# Qwiic_GPS_-_Ublox_SAM-M8Q_-_EAGLE_ARRRG.net
KiCad netlist of a schematic drawn in EAGLE
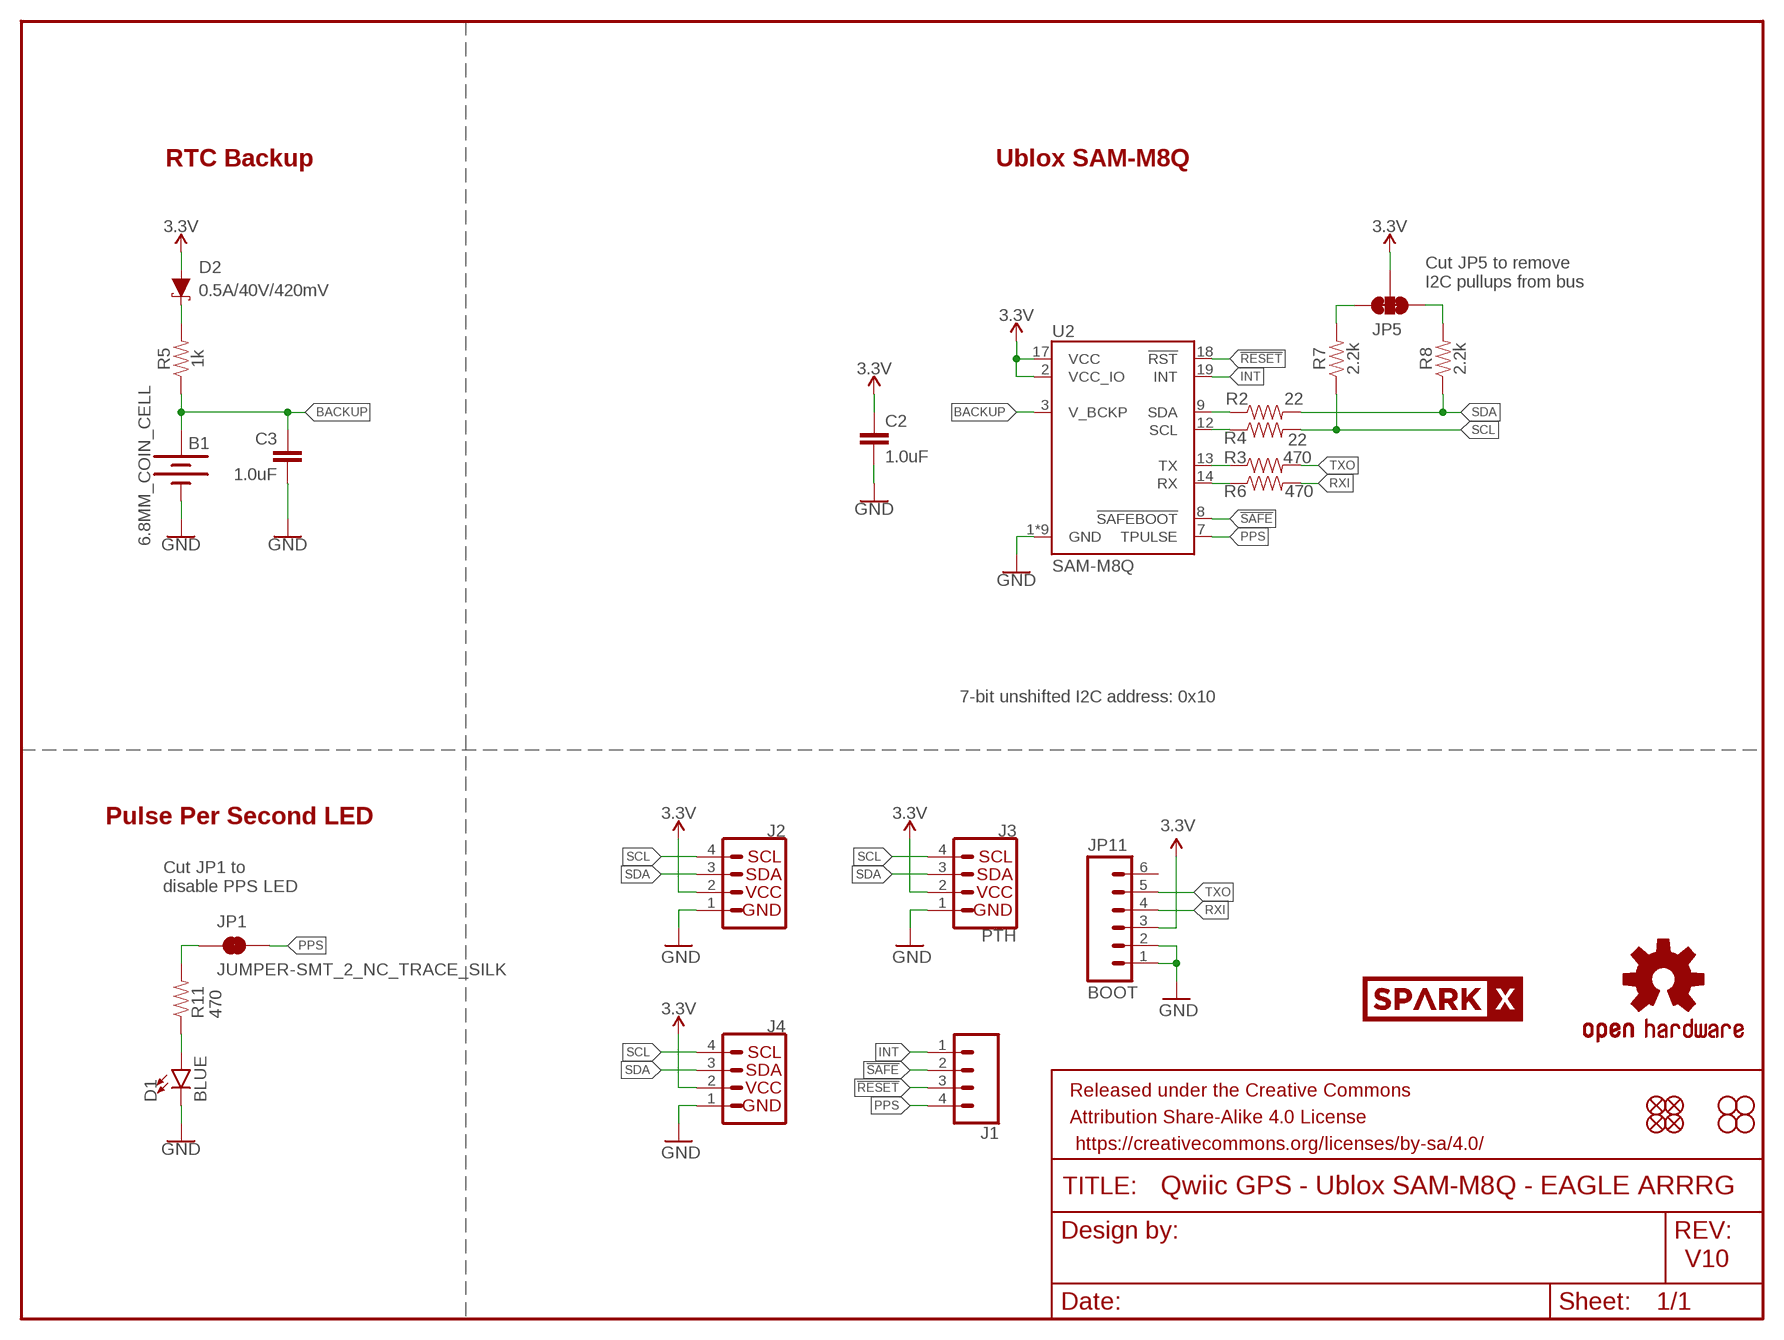
[diagram p0: schematic, sheet 1]

(export (version "E")
  (design (tool "Eeschema 10.0.6"))
  (components
    (comp (ref "B1")
      (value "6.8MM_COIN_CELL")
      (footprint "eagle-import:BATTCON-6.8MM")
      (libsource (lib "eagle-import") (part "BATTERY-6.8MM_SMD"))
    )
    (comp (ref "C2")
      (value "1.0uF")
      (footprint "eagle-import:0603")
      (libsource (lib "eagle-import") (part "1.0UF-0603-16V-10%"))
    )
    (comp (ref "C3")
      (value "1.0uF")
      (footprint "eagle-import:0603")
      (libsource (lib "eagle-import") (part "1.0UF-0603-16V-10%"))
    )
    (comp (ref "D1")
      (value "BLUE")
      (footprint "eagle-import:LED-0603")
      (libsource (lib "eagle-import") (part "LED-BLUE0603"))
    )
    (comp (ref "D2")
      (value "0.5A/40V/420mV")
      (footprint "eagle-import:SOD-323")
      (libsource (lib "eagle-import") (part "DIODE-SCHOTTKY-PMEG4005EJ"))
    )
    (comp (ref "FRAME1")
      (value "FRAME-LETTER")
      (footprint "eagle-import:CREATIVE_COMMONS")
      (libsource (lib "eagle-import") (part "FRAME-LETTER"))
    )
    (comp (ref "J1")
      (value "CONN_041X04_NO_SILK")
      (footprint "eagle-import:1X04_NO_SILK")
      (libsource (lib "eagle-import") (part "CONN_041X04_NO_SILK"))
    )
    (comp (ref "J2")
      (value "I2C_STANDARDQWIIC")
      (footprint "eagle-import:1X04_1MM_RA")
      (libsource (lib "eagle-import") (part "I2C_STANDARDQWIIC"))
    )
    (comp (ref "J3")
      (value "PTH")
      (footprint "eagle-import:1X04_NO_SILK")
      (libsource (lib "eagle-import") (part "SparkX_I2C_STANDARD_NO_SILK"))
    )
    (comp (ref "J4")
      (value "I2C_STANDARDQWIIC")
      (footprint "eagle-import:1X04_1MM_RA")
      (libsource (lib "eagle-import") (part "I2C_STANDARDQWIIC"))
    )
    (comp (ref "JP1")
      (value "JUMPER-SMT_2_NC_TRACE_SILK")
      (footprint "eagle-import:SMT-JUMPER_2_NC_TRACE_SILK")
      (libsource (lib "eagle-import") (part "JUMPER-SMT_2_NC_TRACE_SILK"))
    )
    (comp (ref "JP2")
      (value "FIDUCIALUFIDUCIAL")
      (footprint "eagle-import:MICRO-FIDUCIAL")
      (libsource (lib "eagle-import") (part "FIDUCIALUFIDUCIAL"))
    )
    (comp (ref "JP3")
      (value "STAND-OFF")
      (footprint "eagle-import:STAND-OFF")
      (libsource (lib "eagle-import") (part "STAND-OFF"))
    )
    (comp (ref "JP4")
      (value "STAND-OFF")
      (footprint "eagle-import:STAND-OFF")
      (libsource (lib "eagle-import") (part "STAND-OFF"))
    )
    (comp (ref "JP5")
      (value "JUMPER-SMT_3_2-NC_TRACE_SILK")
      (footprint "eagle-import:SMT-JUMPER_3_2-NC_TRACE_SILK")
      (libsource (lib "eagle-import") (part "JUMPER-SMT_3_2-NC_TRACE_SILK"))
    )
    (comp (ref "JP6")
      (value "FIDUCIALUFIDUCIAL")
      (footprint "eagle-import:MICRO-FIDUCIAL")
      (libsource (lib "eagle-import") (part "FIDUCIALUFIDUCIAL"))
    )
    (comp (ref "JP7")
      (value "FIDUCIALUFIDUCIAL")
      (footprint "eagle-import:MICRO-FIDUCIAL")
      (libsource (lib "eagle-import") (part "FIDUCIALUFIDUCIAL"))
    )
    (comp (ref "JP8")
      (value "FIDUCIALUFIDUCIAL")
      (footprint "eagle-import:MICRO-FIDUCIAL")
      (libsource (lib "eagle-import") (part "FIDUCIALUFIDUCIAL"))
    )
    (comp (ref "JP9")
      (value "STAND-OFF")
      (footprint "eagle-import:STAND-OFF")
      (libsource (lib "eagle-import") (part "STAND-OFF"))
    )
    (comp (ref "JP10")
      (value "STAND-OFF")
      (footprint "eagle-import:STAND-OFF")
      (libsource (lib "eagle-import") (part "STAND-OFF"))
    )
    (comp (ref "JP11")
      (value "BOOT")
      (footprint "eagle-import:1X06_NO_SILK")
      (libsource (lib "eagle-import") (part "M06NO_SILK_FEMALE_PTH"))
    )
    (comp (ref "LOGO1")
      (value "OSHW-LOGOMINI")
      (footprint "eagle-import:OSHW-LOGO-MINI")
      (libsource (lib "eagle-import") (part "OSHW-LOGOMINI"))
    )
    (comp (ref "R2")
      (value "22")
      (footprint "eagle-import:0603")
      (libsource (lib "eagle-import") (part "22OHM-0603-1/10W-1%"))
    )
    (comp (ref "R3")
      (value "470")
      (footprint "eagle-import:0603")
      (libsource (lib "eagle-import") (part "470OHM-0603-1/10W-1%"))
    )
    (comp (ref "R4")
      (value "22")
      (footprint "eagle-import:0603")
      (libsource (lib "eagle-import") (part "22OHM-0603-1/10W-1%"))
    )
    (comp (ref "R5")
      (value "1k")
      (footprint "eagle-import:0603")
      (libsource (lib "eagle-import") (part "1KOHM-0603-1/10W-1%"))
    )
    (comp (ref "R6")
      (value "470")
      (footprint "eagle-import:0603")
      (libsource (lib "eagle-import") (part "470OHM-0603-1/10W-1%"))
    )
    (comp (ref "R7")
      (value "2.2k")
      (footprint "eagle-import:0603")
      (libsource (lib "eagle-import") (part "2.2KOHM-0603-1/10W-1%"))
    )
    (comp (ref "R8")
      (value "2.2k")
      (footprint "eagle-import:0603")
      (libsource (lib "eagle-import") (part "2.2KOHM-0603-1/10W-1%"))
    )
    (comp (ref "R11")
      (value "470")
      (footprint "eagle-import:0603")
      (libsource (lib "eagle-import") (part "470OHM-0603-1/10W-1%"))
    )
    (comp (ref "U$31")
      (value "SPARKX-LOGO4")
      (footprint "eagle-import:SPARKX-MEDIUM")
      (libsource (lib "eagle-import") (part "SPARKX-LOGO4"))
    )
    (comp (ref "U2")
      (value "SAM-M8Q")
      (footprint "eagle-import:SAM-M8Q")
      (libsource (lib "eagle-import") (part "SAM-M8Q"))
    )
  )
  (nets
    (net (code "1") (name "/~{RESET}") (class "Default")
      (node (ref "J1") (pin "3") (pinfunction "3_3") (pintype "passive"))
      (node (ref "U2") (pin "18") (pinfunction "~{RST}_18") (pintype "bidirectional"))
    )
    (net (code "2") (name "/~{SAFE}") (class "Default")
      (node (ref "J1") (pin "2") (pinfunction "2_2") (pintype "passive"))
      (node (ref "U2") (pin "8") (pinfunction "~{SAFEBOOT}_8") (pintype "bidirectional"))
    )
    (net (code "3") (name "3.3V") (class "Default")
      (node (ref "C2") (pin "1") (pinfunction "1_1") (pintype "passive"))
      (node (ref "D2") (pin "A") (pinfunction "A_A") (pintype "passive"))
      (node (ref "J2") (pin "2") (pinfunction "2_2") (pintype "power_in"))
      (node (ref "J3") (pin "2") (pinfunction "VCC_2") (pintype "power_in"))
      (node (ref "J4") (pin "2") (pinfunction "2_2") (pintype "power_in"))
      (node (ref "JP11") (pin "3") (pinfunction "3_3") (pintype "passive"))
      (node (ref "JP5") (pin "2") (pinfunction "2_2") (pintype "passive"))
      (node (ref "U2") (pin "17") (pinfunction "VCC_17") (pintype "bidirectional"))
      (node (ref "U2") (pin "2") (pinfunction "VCC_IO_2") (pintype "bidirectional"))
    )
    (net (code "4") (name "BACKUP") (class "Default")
      (node (ref "B1") (pin "+") (pinfunction "+_+") (pintype "power_in"))
      (node (ref "C3") (pin "1") (pinfunction "1_1") (pintype "passive"))
      (node (ref "R5") (pin "1") (pinfunction "1_1") (pintype "passive"))
      (node (ref "U2") (pin "3") (pinfunction "V_BCKP_3") (pintype "bidirectional"))
    )
    (net (code "5") (name "GND") (class "Default")
      (node (ref "B1") (pin "-") (pinfunction "-_-") (pintype "power_in"))
      (node (ref "C2") (pin "2") (pinfunction "2_2") (pintype "passive"))
      (node (ref "C3") (pin "2") (pinfunction "2_2") (pintype "passive"))
      (node (ref "D1") (pin "C") (pinfunction "C_C") (pintype "passive"))
      (node (ref "J2") (pin "1") (pinfunction "1_1") (pintype "power_in"))
      (node (ref "J3") (pin "1") (pinfunction "GND_1") (pintype "power_in"))
      (node (ref "J4") (pin "1") (pinfunction "1_1") (pintype "power_in"))
      (node (ref "JP11") (pin "1") (pinfunction "1_1") (pintype "passive"))
      (node (ref "JP11") (pin "2") (pinfunction "2_2") (pintype "passive"))
      (node (ref "U2") (pin "1") (pinfunction "GND_1") (pintype "bidirectional"))
      (node (ref "U2") (pin "10") (pinfunction "GND_10") (pintype "bidirectional"))
      (node (ref "U2") (pin "11") (pinfunction "GND_11") (pintype "bidirectional"))
      (node (ref "U2") (pin "15") (pinfunction "GND_15") (pintype "bidirectional"))
      (node (ref "U2") (pin "16") (pinfunction "GND_16") (pintype "bidirectional"))
      (node (ref "U2") (pin "20") (pinfunction "GND_20") (pintype "bidirectional"))
      (node (ref "U2") (pin "4") (pinfunction "GND_4") (pintype "bidirectional"))
      (node (ref "U2") (pin "5") (pinfunction "GND_5") (pintype "bidirectional"))
      (node (ref "U2") (pin "6") (pinfunction "GND_6") (pintype "bidirectional"))
    )
    (net (code "6") (name "INT") (class "Default")
      (node (ref "J1") (pin "1") (pinfunction "1_1") (pintype "passive"))
      (node (ref "U2") (pin "19") (pinfunction "INT_19") (pintype "bidirectional"))
    )
    (net (code "7") (name "Net-(D1-PadA)") (class "Default")
      (node (ref "D1") (pin "A") (pinfunction "A_A") (pintype "passive"))
      (node (ref "R11") (pin "1") (pinfunction "1_1") (pintype "passive"))
    )
    (net (code "8") (name "Net-(D2-PadC)") (class "Default")
      (node (ref "D2") (pin "C") (pinfunction "C_C") (pintype "passive"))
      (node (ref "R5") (pin "2") (pinfunction "2_2") (pintype "passive"))
    )
    (net (code "9") (name "Net-(JP1-Pad1)") (class "Default")
      (node (ref "JP1") (pin "1") (pinfunction "1_1") (pintype "passive"))
      (node (ref "R11") (pin "2") (pinfunction "2_2") (pintype "passive"))
    )
    (net (code "10") (name "Net-(JP5-Pad1)") (class "Default")
      (node (ref "JP5") (pin "1") (pinfunction "1_1") (pintype "passive"))
      (node (ref "R8") (pin "2") (pinfunction "2_2") (pintype "passive"))
    )
    (net (code "11") (name "Net-(JP5-Pad3)") (class "Default")
      (node (ref "JP5") (pin "3") (pinfunction "3_3") (pintype "passive"))
      (node (ref "R7") (pin "2") (pinfunction "2_2") (pintype "passive"))
    )
    (net (code "12") (name "Net-(U2-RX)") (class "Default")
      (node (ref "R6") (pin "1") (pinfunction "1_1") (pintype "passive"))
      (node (ref "U2") (pin "14") (pinfunction "RX_14") (pintype "bidirectional"))
    )
    (net (code "13") (name "Net-(U2-SCL)") (class "Default")
      (node (ref "R4") (pin "1") (pinfunction "1_1") (pintype "passive"))
      (node (ref "U2") (pin "12") (pinfunction "SCL_12") (pintype "bidirectional"))
    )
    (net (code "14") (name "Net-(U2-SDA)") (class "Default")
      (node (ref "R2") (pin "1") (pinfunction "1_1") (pintype "passive"))
      (node (ref "U2") (pin "9") (pinfunction "SDA_9") (pintype "bidirectional"))
    )
    (net (code "15") (name "Net-(U2-TX)") (class "Default")
      (node (ref "R3") (pin "1") (pinfunction "1_1") (pintype "passive"))
      (node (ref "U2") (pin "13") (pinfunction "TX_13") (pintype "bidirectional"))
    )
    (net (code "16") (name "PPS") (class "Default")
      (node (ref "J1") (pin "4") (pinfunction "4_4") (pintype "passive"))
      (node (ref "JP1") (pin "2") (pinfunction "2_2") (pintype "passive"))
      (node (ref "U2") (pin "7") (pinfunction "TPULSE_7") (pintype "bidirectional"))
    )
    (net (code "17") (name "RXI") (class "Default")
      (node (ref "JP11") (pin "4") (pinfunction "4_4") (pintype "passive"))
      (node (ref "R6") (pin "2") (pinfunction "2_2") (pintype "passive"))
    )
    (net (code "18") (name "SCL") (class "Default")
      (node (ref "J2") (pin "4") (pinfunction "4_4") (pintype "passive"))
      (node (ref "J3") (pin "4") (pinfunction "SCL_4") (pintype "passive"))
      (node (ref "J4") (pin "4") (pinfunction "4_4") (pintype "passive"))
      (node (ref "R4") (pin "2") (pinfunction "2_2") (pintype "passive"))
      (node (ref "R7") (pin "1") (pinfunction "1_1") (pintype "passive"))
    )
    (net (code "19") (name "SDA") (class "Default")
      (node (ref "J2") (pin "3") (pinfunction "3_3") (pintype "passive"))
      (node (ref "J3") (pin "3") (pinfunction "SDA_3") (pintype "passive"))
      (node (ref "J4") (pin "3") (pinfunction "3_3") (pintype "passive"))
      (node (ref "R2") (pin "2") (pinfunction "2_2") (pintype "passive"))
      (node (ref "R8") (pin "1") (pinfunction "1_1") (pintype "passive"))
    )
    (net (code "20") (name "TXO") (class "Default")
      (node (ref "JP11") (pin "5") (pinfunction "5_5") (pintype "passive"))
      (node (ref "R3") (pin "2") (pinfunction "2_2") (pintype "passive"))
    )
    (net (code "21") (name "unconnected-(JP11-Pad6)") (class "Default")
      (node (ref "JP11") (pin "6") (pinfunction "6_6") (pintype "passive"))
    )
  )
)
